# TCSB.net
KiCad netlist of a schematic drawn in EAGLE
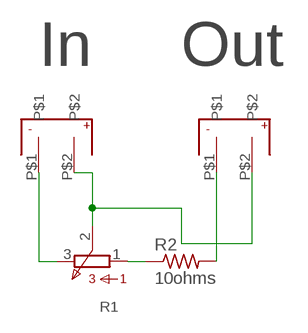
[diagram p0: schematic, sheet 1]

(export (version "E")
  (design (tool "Eeschema 10.0.6"))
  (components
    (comp (ref "R1")
      (value "308/309")
      (footprint "eagle-import:308")
      (libsource (lib "eagle-import") (part "308/309"))
    )
    (comp (ref "R2")
      (value "10ohms")
      (footprint "eagle-import:0204_7")
      (libsource (lib "eagle-import") (part "R-US_0204/7"))
    )
    (comp (ref "U$1")
      (value "RCA-YELLOW")
      (footprint "eagle-import:RCA-YELLOW")
      (libsource (lib "eagle-import") (part "RCA-YELLOW"))
    )
    (comp (ref "U$2")
      (value "RCA-YELLOW")
      (footprint "eagle-import:RCA-YELLOW")
      (libsource (lib "eagle-import") (part "RCA-YELLOW"))
    )
  )
  (nets
    (net (code "1") (name "Net-(R1-Pad1)") (class "Default")
      (node (ref "R1") (pin "1") (pinfunction "1_1") (pintype "passive"))
      (node (ref "R2") (pin "1") (pinfunction "1_1") (pintype "passive"))
    )
    (net (code "2") (name "Net-(R1-Pad2)") (class "Default")
      (node (ref "R1") (pin "2") (pinfunction "2_2") (pintype "passive"))
      (node (ref "U$1") (pin "P$2") (pinfunction "P$2_P$2") (pintype "bidirectional"))
      (node (ref "U$2") (pin "P$2") (pinfunction "P$2_P$2") (pintype "bidirectional"))
    )
    (net (code "3") (name "Net-(R1-Pad3)") (class "Default")
      (node (ref "R1") (pin "3") (pinfunction "3_3") (pintype "passive"))
      (node (ref "U$1") (pin "P$1") (pinfunction "P$1_P$1") (pintype "bidirectional"))
    )
    (net (code "4") (name "Net-(R2-Pad2)") (class "Default")
      (node (ref "R2") (pin "2") (pinfunction "2_2") (pintype "passive"))
      (node (ref "U$2") (pin "P$1") (pinfunction "P$1_P$1") (pintype "bidirectional"))
    )
  )
)
